# mechanical.net
KiCad netlist of a schematic drawn in Altium Designer
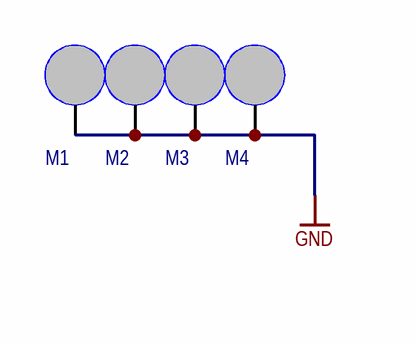
[diagram p0: mechanical.SchDoc]

(export (version "E")
  (design (tool "Eeschema 10.0.6"))
  (components
    (comp (ref "M1")
      (value "MOUNTM3_CORNERS")
      (footprint "MOUNTM3_CORNERS")
      (libsource (lib "generic") (part "MOUNT"))
    )
    (comp (ref "M2")
      (value "MOUNTM3_CORNERS")
      (footprint "MOUNTM3_CORNERS")
      (libsource (lib "generic") (part "MOUNT"))
    )
    (comp (ref "M3")
      (value "MOUNTM3_CORNERS")
      (footprint "MOUNTM3_CORNERS")
      (libsource (lib "generic") (part "MOUNT"))
    )
    (comp (ref "M4")
      (value "MOUNTM3_CORNERS")
      (footprint "MOUNTM3_CORNERS")
      (libsource (lib "generic") (part "MOUNT"))
    )
  )
  (nets
    (net (code "1") (name "GND") (class "Default")
      (node (ref "M1") (pin "1") (pinfunction "MNT_1") (pintype "passive"))
      (node (ref "M2") (pin "1") (pinfunction "MNT_1") (pintype "passive"))
      (node (ref "M3") (pin "1") (pinfunction "MNT_1") (pintype "passive"))
      (node (ref "M4") (pin "1") (pinfunction "MNT_1") (pintype "passive"))
    )
  )
)
